# Buck.net
KiCad netlist of a schematic drawn in Altium Designer
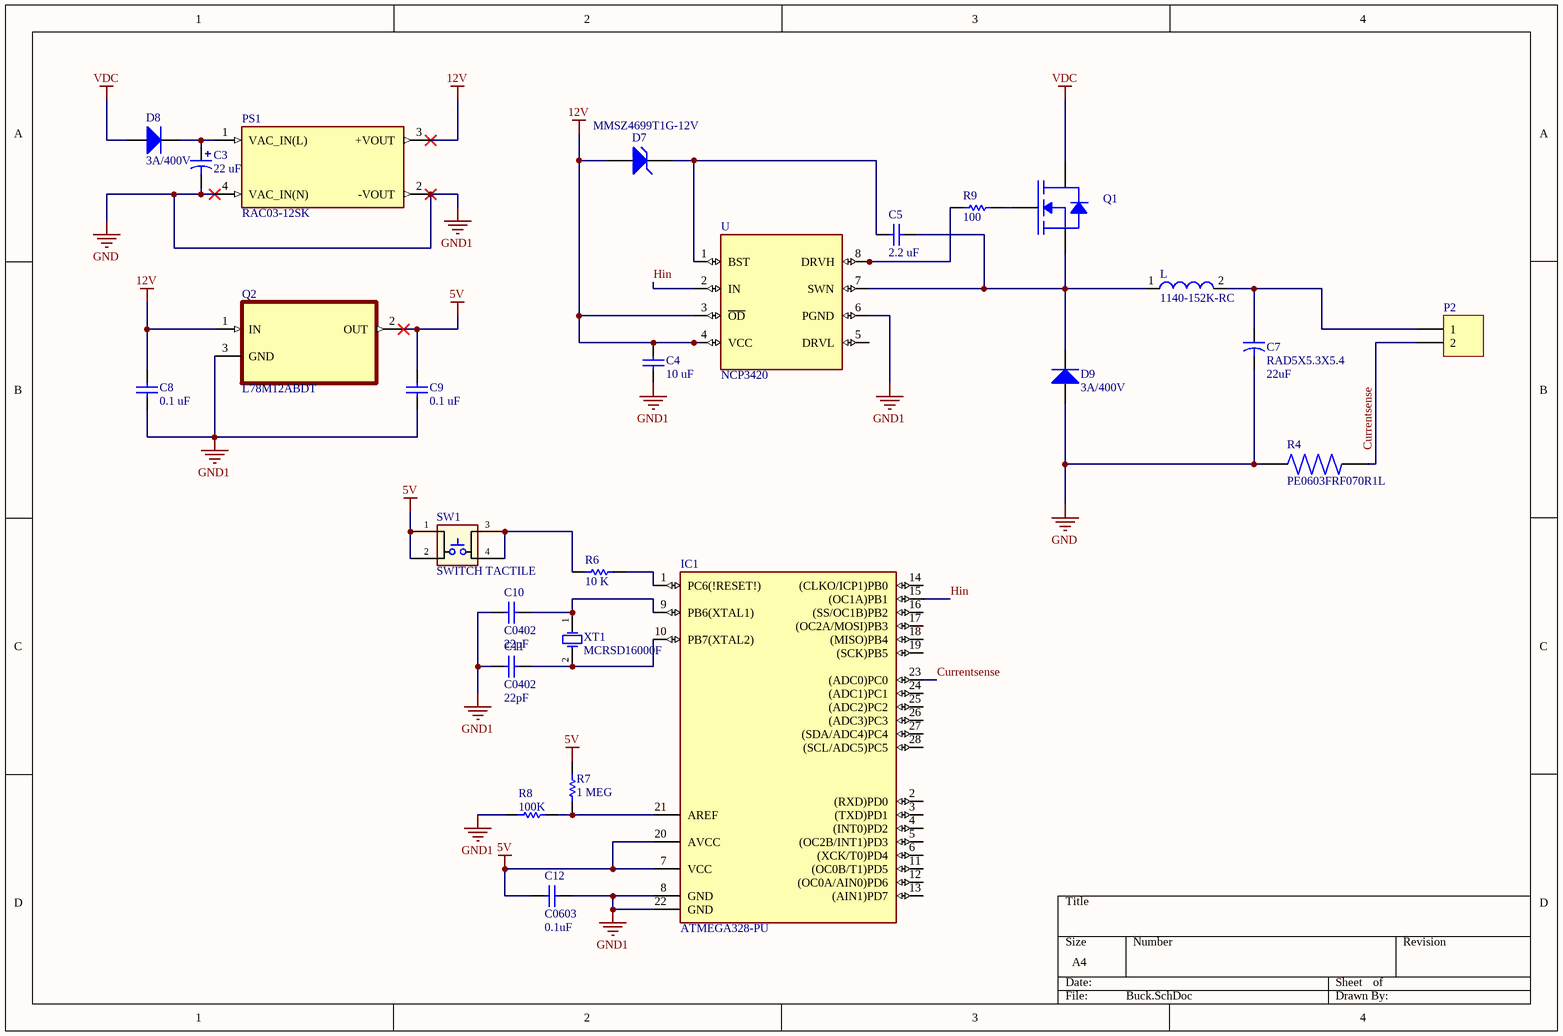
[diagram p0: Buck.SchDoc]

(export (version "E")
  (design (tool "Eeschema 10.0.6"))
  (components
    (comp (ref "C3")
      (value "22 uF")
      (footprint "CAP-12.25X25")
      (description "22 uF Electrlytic capacitor")
      (fields (field (name "Comment") "EEUED2G220") (field (name "PUBLISHER") "Altium Limited"))
      (libsource (lib "Viva") (part "EEUED2G220"))
    )
    (comp (ref "C4")
      (value "10 uF")
      (footprint "1206")
      (description "10 uF X7R Ceremic Capacitor")
      (fields (field (name "Comment") "MC1206B106K160CT") (field (name "PUBLISHER") "Sinan"))
      (libsource (lib "Viva") (part "MC1206B106K160CT"))
    )
    (comp (ref "C5")
      (value "2.2 uF")
      (footprint "0805")
      (description "2.2 uF X7R Ceremic Capacitor")
      (fields
        (field (name "TOLERANCE") "%10")
        (field (name "Comment") "C2012X7R1C225K")
        (field (name "PUBLISHER") "Sinan")
      )
      (libsource (lib "Viva") (part "C2012X7R1C225K"))
    )
    (comp (ref "C7")
      (value "22uF")
      (footprint "RAD5.3X5.3X5.0")
      (description "CAP ALUM 22UF 20% 35V SMD 5X5.3X5.4")
      (fields (field (name "MANUFACTURER") "PANASONIC") (field (name "PACKAGE REFERENCE") "RAD5X5.3X5.4"))
      (libsource (lib "CAPACITOR_LIB") (part "CAP ALUM 22UF 20% 35V SMD 5X5.3X5.4"))
    )
    (comp (ref "C8")
      (value "0.1 uF")
      (footprint "0603")
      (description "0.1uF X7R Ceramic Capacitor")
      (fields
        (field (name "TOLERANCE") "%5")
        (field (name "Comment") "*Value")
        (field (name "PUBLISHER") "Baris")
      )
      (libsource (lib "Viva") (part "C0603C104K3RACTU"))
    )
    (comp (ref "C9")
      (value "0.1 uF")
      (footprint "0603")
      (description "0.1uF X7R Ceramic Capacitor")
      (fields
        (field (name "TOLERANCE") "%5")
        (field (name "Comment") "*Value")
        (field (name "PUBLISHER") "Baris")
      )
      (libsource (lib "Viva") (part "C0603C104K3RACTU"))
    )
    (comp (ref "C10")
      (value "22pF")
      (footprint "C0402N")
      (description "CAP CER 22PF 5% 50V NP0 SMD 0402")
      (fields (field (name "MANUFACTURER") "SAMSUNG ELECTRO") (field (name "PACKAGE REFERENCE") "C0402"))
      (libsource (lib "CAPACITOR_LIB") (part "CAP CER 22PF 5% 50V NP0 SMD 0402"))
    )
    (comp (ref "C11")
      (value "22pF")
      (footprint "C0402N")
      (description "CAP CER 22PF 5% 50V NP0 SMD 0402")
      (fields (field (name "MANUFACTURER") "SAMSUNG ELECTRO") (field (name "PACKAGE REFERENCE") "C0402"))
      (libsource (lib "CAPACITOR_LIB") (part "CAP CER 22PF 5% 50V NP0 SMD 0402"))
    )
    (comp (ref "C12")
      (value "0.1uF")
      (footprint "C0603N")
      (description "CAP CER 0.1UF 10% 16V X7R SMD 0603")
      (fields (field (name "MANUFACTURER") "MURATA") (field (name "PACKAGE REFERENCE") "C0603"))
      (libsource (lib "CAPACITOR_LIB") (part "CAP CER 0.1UF 10% 16V X7R SMD 0603"))
    )
    (comp (ref "D7")
      (value "MMSZ4699T1G-12V")
      (footprint "SOD123")
      (description "DIODE ZENER 12V 500MW SOD123")
      (fields (field (name "PUBLISHER") "Baris"))
      (libsource (lib "Viva") (part "MMSZ4699T1G"))
    )
    (comp (ref "D8")
      (value "3A/400V")
      (footprint "DO201AD")
      (description "DIODE GEN PURP 400V 3A DO201AD")
      (fields
        (field (name "MANUFACTURER") "DIODES INC.")
        (field (name "Comment") "DIODE GEN PURP 400V 3A DO201AD - 1N5404")
      )
      (libsource (lib "DISCRETE_LIB") (part "DIODE GEN PURP 400V 3A DO201AD - 1N5404"))
    )
    (comp (ref "D9")
      (value "3A/400V")
      (footprint "DO201AD")
      (description "DIODE GEN PURP 400V 3A DO201AD")
      (fields
        (field (name "MANUFACTURER") "DIODES INC.")
        (field (name "Comment") "DIODE GEN PURP 400V 3A DO201AD - 1N5404")
      )
      (libsource (lib "DISCRETE_LIB") (part "DIODE GEN PURP 400V 3A DO201AD - 1N5404"))
    )
    (comp (ref "IC1")
      (value "ATMEGA328-PU")
      (footprint "DIL28")
      (description "AVR AVRÂ® ATmega Microcontroller IC 8-Bit 20MHz 32KB _16K x 16_ FLASH 28-PDIP")
      (fields (field (name "MF") "Microchip Technology"))
      (libsource (lib "Viva") (part "ATMEGA328-PU"))
    )
    (comp (ref "L")
      (value "1140-152K-RC")
      (footprint "INDRD2921W163D3810H2616P")
      (description "1.5mH Unshielded Wirewound Inductor 2.9A 324mOhm Max Radial")
      (fields (field (name "MF") "Bourns"))
      (libsource (lib "Viva") (part "1140-152K-RC"))
    )
    (comp (ref "P2")
      (value "Konnektör")
      (footprint "250-202")
      (description "2 pos power connector")
      (fields (field (name "PUBLISHER") "Sinan"))
      (libsource (lib "Viva") (part "250-202"))
    )
    (comp (ref "PS1")
      (value "RAC03-12SK")
      (footprint "CONV_RAC03-12SK")
      (description "Enclosed AC DC Converters 1 Uitgang 12V 250mA 85 ~ 264 VAC, 120 ~ 370 VDC Input")
      (fields (field (name "MF") "Recom Power"))
      (libsource (lib "Viva") (part "RAC03-12SK"))
    )
    (comp (ref "Q1")
      (value "LSIC1MO120E0080")
      (footprint "TO-247-3L")
      (description "LittleFuse SIC mosfet")
      (fields (field (name "PUBLISHER") "Baris"))
      (libsource (lib "Viva") (part "LSIC1MO120E0080"))
    )
    (comp (ref "Q2")
      (value "L78M12ABDT")
      (footprint "TO225P972X240-3N")
      (description "Linear Voltage Regulator IC 1 Output 500mA DPAK")
      (fields (field (name "MF") "STMicroelectronics"))
      (libsource (lib "L78M12ABDT") (part "L78M12ABDT"))
    )
    (comp (ref "R4")
      (value "PE0603FRF070R1L")
      (footprint "RESC1507X55N")
      (libsource (lib "PE0603FRF070R1L") (part "PE0603FRF070R1L"))
    )
    (comp (ref "R6")
      (value "10 K")
      (footprint "0603")
      (description "10k ohm 0603 package resistor")
      (fields
        (field (name "TOLERANCE") "5%")
        (field (name "Comment") "ERJ3GEYJ103V")
        (field (name "PUBLISHER") "Sinan")
      )
      (libsource (lib "Viva") (part "ERJ3GEYJ103V"))
    )
    (comp (ref "R7")
      (value "1 MEG")
      (footprint "0603")
      (description "1 MEG ohm 0603 package resistor")
      (fields (field (name "Comment") "Resistor") (field (name "PUBLISHER") "Sinan"))
      (libsource (lib "Viva") (part "MC0063W060311M"))
    )
    (comp (ref "R8")
      (value "100K")
      (footprint "0603")
      (description "100Kohm 0603package resistor")
      (fields (field (name "Comment") "MC0063W06031100K") (field (name "PUBLISHER") "Baris"))
      (libsource (lib "Viva") (part "MC0063W06031100K"))
    )
    (comp (ref "R9")
      (value "100")
      (footprint "1206")
      (description "100 ohm 1206 package resistor")
      (fields (field (name "Comment") "*Value") (field (name "PUBLISHER") "Baris"))
      (libsource (lib "Viva") (part "MC0125W12061100R"))
    )
    (comp (ref "SW1")
      (value "SWITCH TACTILE")
      (footprint "SWITCH_TACHTILE_SMD")
      (description "SWITCH TACTILE (SPST NO) TOP ACTUATED SURFACE MOUNT")
      (fields (field (name "MANUFACTURER") "C&K Components"))
      (libsource (lib "CONNECTOR_LIB") (part "SWITCH TACTILE"))
    )
    (comp (ref "U")
      (value "NCP3420")
      (footprint "SO08")
      (description "ON Semiconductor TSMC 12V FET DRVR")
      (fields (field (name "MF") "ON Semiconductor"))
      (libsource (lib "Viva") (part "NCP3420"))
    )
    (comp (ref "XT1")
      (value "MCRSD16000F")
      (footprint "XTAL_11.4MMX 4.7MM")
      (description "CRYSTAL 16MHZ 18PF")
      (fields (field (name "MANUFACTURER") "MULTICOMP"))
      (libsource (lib "DISCRETE_LIB") (part "CRYSTAL 16MHZ 18PF"))
    )
  )
  (nets
    (net (code "1") (name "/Currentsense") (class "Default")
      (node (ref "IC1") (pin "23") (pinfunction "(ADC0)PC0_23") (pintype "bidirectional"))
      (node (ref "P2") (pin "2") (pinfunction "2_2") (pintype "passive"))
      (node (ref "R4") (pin "1") (pinfunction "1_1") (pintype "passive"))
    )
    (net (code "2") (name "/Hin") (class "Default")
      (node (ref "IC1") (pin "15") (pinfunction "(OC1A)PB1_15") (pintype "bidirectional"))
      (node (ref "U") (pin "2") (pinfunction "IN_2") (pintype "bidirectional"))
    )
    (net (code "3") (name "5V") (class "Default")
      (node (ref "C12") (pin "1") (pinfunction "1_1") (pintype "passive"))
      (node (ref "C9") (pin "2") (pinfunction "2_2") (pintype "passive"))
      (node (ref "IC1") (pin "20") (pinfunction "AVCC_20") (pintype "power_in"))
      (node (ref "IC1") (pin "7") (pinfunction "VCC_7") (pintype "power_in"))
      (node (ref "Q2") (pin "2") (pinfunction "OUT_2") (pintype "output"))
      (node (ref "R7") (pin "2") (pinfunction "2_2") (pintype "passive"))
      (node (ref "SW1") (pin "1") (pinfunction "1_1") (pintype "passive"))
      (node (ref "SW1") (pin "2") (pinfunction "2_2") (pintype "passive"))
    )
    (net (code "4") (name "12V") (class "Default")
      (node (ref "C4") (pin "1") (pinfunction "1_1") (pintype "passive"))
      (node (ref "C8") (pin "2") (pinfunction "2_2") (pintype "passive"))
      (node (ref "D7") (pin "1") (pinfunction "A_1") (pintype "passive"))
      (node (ref "PS1") (pin "3") (pinfunction "+VOUT_3") (pintype "output"))
      (node (ref "Q2") (pin "1") (pinfunction "IN_1") (pintype "input"))
      (node (ref "U") (pin "3") (pinfunction "~{OD}_3") (pintype "bidirectional"))
      (node (ref "U") (pin "4") (pinfunction "VCC_4") (pintype "bidirectional"))
    )
    (net (code "5") (name "GND") (class "Default")
      (node (ref "C10") (pin "1") (pinfunction "1_1") (pintype "passive"))
      (node (ref "C11") (pin "1") (pinfunction "1_1") (pintype "passive"))
      (node (ref "C12") (pin "2") (pinfunction "2_2") (pintype "passive"))
      (node (ref "C3") (pin "2") (pinfunction "2_2") (pintype "passive"))
      (node (ref "C4") (pin "2") (pinfunction "2_2") (pintype "passive"))
      (node (ref "C7") (pin "2") (pinfunction "2_2") (pintype "passive"))
      (node (ref "C8") (pin "1") (pinfunction "1_1") (pintype "passive"))
      (node (ref "C9") (pin "1") (pinfunction "1_1") (pintype "passive"))
      (node (ref "D9") (pin "1") (pinfunction "A_1") (pintype "passive"))
      (node (ref "IC1") (pin "22") (pinfunction "GND_22") (pintype "power_in"))
      (node (ref "IC1") (pin "8") (pinfunction "GND_8") (pintype "power_in"))
      (node (ref "PS1") (pin "2") (pinfunction "-VOUT_2") (pintype "output"))
      (node (ref "PS1") (pin "4") (pinfunction "VAC_IN(N)_4") (pintype "input"))
      (node (ref "Q2") (pin "3") (pinfunction "GND_3") (pintype "passive"))
      (node (ref "R4") (pin "2") (pinfunction "2_2") (pintype "passive"))
      (node (ref "R8") (pin "2") (pinfunction "2_2") (pintype "passive"))
      (node (ref "U") (pin "6") (pinfunction "PGND_6") (pintype "bidirectional"))
    )
    (net (code "6") (name "Net-(C7-Pad1)") (class "Default")
      (node (ref "C7") (pin "1") (pinfunction "1_1") (pintype "passive"))
      (node (ref "L") (pin "2") (pinfunction "2_2") (pintype "passive"))
      (node (ref "P2") (pin "1") (pinfunction "1_1") (pintype "passive"))
    )
    (net (code "7") (name "Net-(D7-K)") (class "Default")
      (node (ref "C5") (pin "1") (pinfunction "1_1") (pintype "passive"))
      (node (ref "D7") (pin "2") (pinfunction "K_2") (pintype "passive"))
      (node (ref "U") (pin "1") (pinfunction "BST_1") (pintype "bidirectional"))
    )
    (net (code "8") (name "Net-(D8-K)") (class "Default")
      (node (ref "C3") (pin "1") (pinfunction "1_1") (pintype "passive"))
      (node (ref "D8") (pin "2") (pinfunction "K_2") (pintype "passive"))
      (node (ref "PS1") (pin "1") (pinfunction "VAC_IN(L)_1") (pintype "input"))
    )
    (net (code "9") (name "Net-(D9-K)") (class "Default")
      (node (ref "C5") (pin "2") (pinfunction "2_2") (pintype "passive"))
      (node (ref "D9") (pin "2") (pinfunction "K_2") (pintype "passive"))
      (node (ref "L") (pin "1") (pinfunction "1_1") (pintype "passive"))
      (node (ref "Q1") (pin "3") (pinfunction "S_3") (pintype "passive"))
      (node (ref "U") (pin "7") (pinfunction "SWN_7") (pintype "bidirectional"))
    )
    (net (code "10") (name "Net-(IC1-AREF)") (class "Default")
      (node (ref "IC1") (pin "21") (pinfunction "AREF_21") (pintype "passive"))
      (node (ref "R7") (pin "1") (pinfunction "1_1") (pintype "passive"))
      (node (ref "R8") (pin "1") (pinfunction "1_1") (pintype "passive"))
    )
    (net (code "11") (name "Net-(IC1-PB6(XTAL1))") (class "Default")
      (node (ref "C10") (pin "2") (pinfunction "2_2") (pintype "passive"))
      (node (ref "IC1") (pin "9") (pinfunction "PB6(XTAL1)_9") (pintype "bidirectional"))
      (node (ref "XT1") (pin "1") (pinfunction "OSC1_1") (pintype "passive"))
    )
    (net (code "12") (name "Net-(IC1-PB7(XTAL2))") (class "Default")
      (node (ref "C11") (pin "2") (pinfunction "2_2") (pintype "passive"))
      (node (ref "IC1") (pin "10") (pinfunction "PB7(XTAL2)_10") (pintype "bidirectional"))
      (node (ref "XT1") (pin "2") (pinfunction "OSC2_2") (pintype "passive"))
    )
    (net (code "13") (name "Net-(IC1-PC6(!RESET!))") (class "Default")
      (node (ref "IC1") (pin "1") (pinfunction "PC6(!RESET!)_1") (pintype "bidirectional"))
      (node (ref "R6") (pin "1") (pinfunction "1_1") (pintype "passive"))
    )
    (net (code "14") (name "Net-(Q1-G)") (class "Default")
      (node (ref "Q1") (pin "1") (pinfunction "G_1") (pintype "passive"))
      (node (ref "R9") (pin "2") (pinfunction "2_2") (pintype "passive"))
    )
    (net (code "15") (name "Net-(R6-Pad2)") (class "Default")
      (node (ref "R6") (pin "2") (pinfunction "2_2") (pintype "passive"))
      (node (ref "SW1") (pin "3") (pinfunction "3_3") (pintype "passive"))
      (node (ref "SW1") (pin "4") (pinfunction "4_4") (pintype "passive"))
    )
    (net (code "16") (name "Net-(U-DRVH)") (class "Default")
      (node (ref "R9") (pin "1") (pinfunction "1_1") (pintype "passive"))
      (node (ref "U") (pin "8") (pinfunction "DRVH_8") (pintype "bidirectional"))
    )
    (net (code "17") (name "VDC") (class "Default")
      (node (ref "D8") (pin "1") (pinfunction "A_1") (pintype "passive"))
      (node (ref "Q1") (pin "2") (pinfunction "D(Tab)_2") (pintype "passive"))
    )
    (net (code "18") (name "unconnected-(IC1-(ADC1)PC1-Pad24)") (class "Default")
      (node (ref "IC1") (pin "24") (pinfunction "(ADC1)PC1_24") (pintype "bidirectional"))
    )
    (net (code "19") (name "unconnected-(IC1-(ADC2)PC2-Pad25)") (class "Default")
      (node (ref "IC1") (pin "25") (pinfunction "(ADC2)PC2_25") (pintype "bidirectional"))
    )
    (net (code "20") (name "unconnected-(IC1-(ADC3)PC3-Pad26)") (class "Default")
      (node (ref "IC1") (pin "26") (pinfunction "(ADC3)PC3_26") (pintype "bidirectional"))
    )
    (net (code "21") (name "unconnected-(IC1-(AIN1)PD7-Pad13)") (class "Default")
      (node (ref "IC1") (pin "13") (pinfunction "(AIN1)PD7_13") (pintype "bidirectional"))
    )
    (net (code "22") (name "unconnected-(IC1-(CLKO{slash}ICP1)PB0-Pad14)") (class "Default")
      (node (ref "IC1") (pin "14") (pinfunction "(CLKO/ICP1)PB0_14") (pintype "bidirectional"))
    )
    (net (code "23") (name "unconnected-(IC1-(INT0)PD2-Pad4)") (class "Default")
      (node (ref "IC1") (pin "4") (pinfunction "(INT0)PD2_4") (pintype "bidirectional"))
    )
    (net (code "24") (name "unconnected-(IC1-(MISO)PB4-Pad18)") (class "Default")
      (node (ref "IC1") (pin "18") (pinfunction "(MISO)PB4_18") (pintype "bidirectional"))
    )
    (net (code "25") (name "unconnected-(IC1-(OC0A{slash}AIN0)PD6-Pad12)") (class "Default")
      (node (ref "IC1") (pin "12") (pinfunction "(OC0A/AIN0)PD6_12") (pintype "bidirectional"))
    )
    (net (code "26") (name "unconnected-(IC1-(OC0B{slash}T1)PD5-Pad11)") (class "Default")
      (node (ref "IC1") (pin "11") (pinfunction "(OC0B/T1)PD5_11") (pintype "bidirectional"))
    )
    (net (code "27") (name "unconnected-(IC1-(OC2A{slash}MOSI)PB3-Pad17)") (class "Default")
      (node (ref "IC1") (pin "17") (pinfunction "(OC2A/MOSI)PB3_17") (pintype "bidirectional"))
    )
    (net (code "28") (name "unconnected-(IC1-(OC2B{slash}INT1)PD3-Pad5)") (class "Default")
      (node (ref "IC1") (pin "5") (pinfunction "(OC2B/INT1)PD3_5") (pintype "bidirectional"))
    )
    (net (code "29") (name "unconnected-(IC1-(RXD)PD0-Pad2)") (class "Default")
      (node (ref "IC1") (pin "2") (pinfunction "(RXD)PD0_2") (pintype "bidirectional"))
    )
    (net (code "30") (name "unconnected-(IC1-(SCK)PB5-Pad19)") (class "Default")
      (node (ref "IC1") (pin "19") (pinfunction "(SCK)PB5_19") (pintype "bidirectional"))
    )
    (net (code "31") (name "unconnected-(IC1-(SCL{slash}ADC5)PC5-Pad28)") (class "Default")
      (node (ref "IC1") (pin "28") (pinfunction "(SCL/ADC5)PC5_28") (pintype "bidirectional"))
    )
    (net (code "32") (name "unconnected-(IC1-(SDA{slash}ADC4)PC4-Pad27)") (class "Default")
      (node (ref "IC1") (pin "27") (pinfunction "(SDA/ADC4)PC4_27") (pintype "bidirectional"))
    )
    (net (code "33") (name "unconnected-(IC1-(SS{slash}OC1B)PB2-Pad16)") (class "Default")
      (node (ref "IC1") (pin "16") (pinfunction "(SS/OC1B)PB2_16") (pintype "bidirectional"))
    )
    (net (code "34") (name "unconnected-(IC1-(TXD)PD1-Pad3)") (class "Default")
      (node (ref "IC1") (pin "3") (pinfunction "(TXD)PD1_3") (pintype "bidirectional"))
    )
    (net (code "35") (name "unconnected-(IC1-(XCK{slash}T0)PD4-Pad6)") (class "Default")
      (node (ref "IC1") (pin "6") (pinfunction "(XCK/T0)PD4_6") (pintype "bidirectional"))
    )
    (net (code "36") (name "unconnected-(U-DRVL-Pad5)") (class "Default")
      (node (ref "U") (pin "5") (pinfunction "DRVL_5") (pintype "bidirectional"))
    )
  )
)
